# USB3_Hub.net
KiCad netlist of a schematic drawn in EAGLE
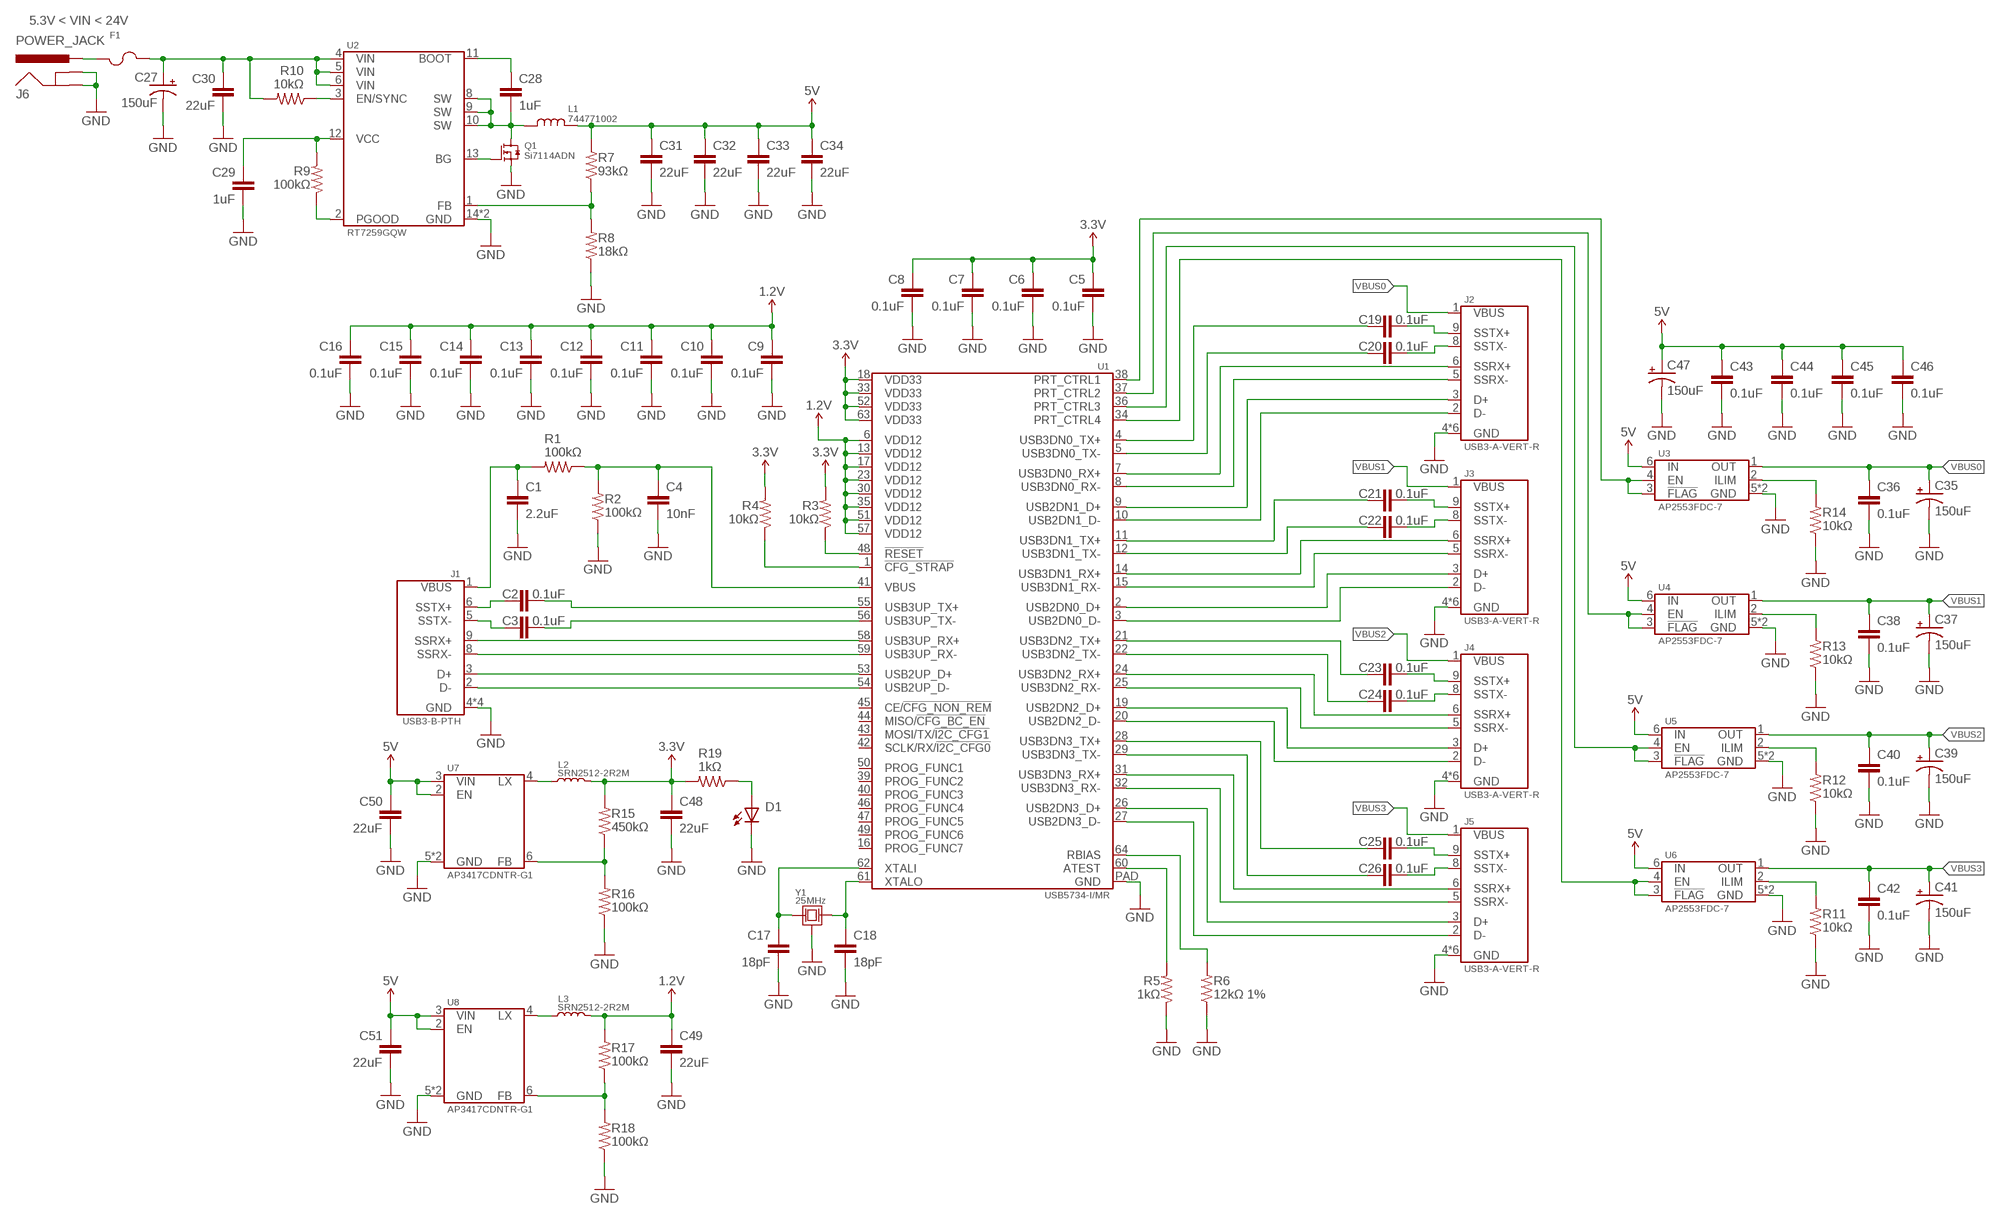
[diagram p0: schematic, sheet 1]

(export (version "E")
  (design (tool "Eeschema 10.0.6"))
  (components
    (comp (ref "C1")
      (value "2.2uF")
      (footprint "eagle-import:0603-CAP")
      (libsource (lib "eagle-import") (part "CAP-0603"))
    )
    (comp (ref "C2")
      (value "0.1uF")
      (footprint "eagle-import:0603-CAP")
      (libsource (lib "eagle-import") (part "CAP-0603"))
    )
    (comp (ref "C3")
      (value "0.1uF")
      (footprint "eagle-import:0603-CAP")
      (libsource (lib "eagle-import") (part "CAP-0603"))
    )
    (comp (ref "C4")
      (value "10nF")
      (footprint "eagle-import:0603-CAP")
      (libsource (lib "eagle-import") (part "CAP-0603"))
    )
    (comp (ref "C5")
      (value "0.1uF")
      (footprint "eagle-import:0603-CAP")
      (libsource (lib "eagle-import") (part "CAP-0603"))
    )
    (comp (ref "C6")
      (value "0.1uF")
      (footprint "eagle-import:0603-CAP")
      (libsource (lib "eagle-import") (part "CAP-0603"))
    )
    (comp (ref "C7")
      (value "0.1uF")
      (footprint "eagle-import:0603-CAP")
      (libsource (lib "eagle-import") (part "CAP-0603"))
    )
    (comp (ref "C8")
      (value "0.1uF")
      (footprint "eagle-import:0603-CAP")
      (libsource (lib "eagle-import") (part "CAP-0603"))
    )
    (comp (ref "C9")
      (value "0.1uF")
      (footprint "eagle-import:0603-CAP")
      (libsource (lib "eagle-import") (part "CAP-0603"))
    )
    (comp (ref "C10")
      (value "0.1uF")
      (footprint "eagle-import:0603-CAP")
      (libsource (lib "eagle-import") (part "CAP-0603"))
    )
    (comp (ref "C11")
      (value "0.1uF")
      (footprint "eagle-import:0603-CAP")
      (libsource (lib "eagle-import") (part "CAP-0603"))
    )
    (comp (ref "C12")
      (value "0.1uF")
      (footprint "eagle-import:0603-CAP")
      (libsource (lib "eagle-import") (part "CAP-0603"))
    )
    (comp (ref "C13")
      (value "0.1uF")
      (footprint "eagle-import:0603-CAP")
      (libsource (lib "eagle-import") (part "CAP-0603"))
    )
    (comp (ref "C14")
      (value "0.1uF")
      (footprint "eagle-import:0603-CAP")
      (libsource (lib "eagle-import") (part "CAP-0603"))
    )
    (comp (ref "C15")
      (value "0.1uF")
      (footprint "eagle-import:0603-CAP")
      (libsource (lib "eagle-import") (part "CAP-0603"))
    )
    (comp (ref "C16")
      (value "0.1uF")
      (footprint "eagle-import:0603-CAP")
      (libsource (lib "eagle-import") (part "CAP-0603"))
    )
    (comp (ref "C17")
      (value "18pF")
      (footprint "eagle-import:0603-CAP")
      (libsource (lib "eagle-import") (part "CAP-0603"))
    )
    (comp (ref "C18")
      (value "18pF")
      (footprint "eagle-import:0603-CAP")
      (libsource (lib "eagle-import") (part "CAP-0603"))
    )
    (comp (ref "C19")
      (value "0.1uF")
      (footprint "eagle-import:0603-CAP")
      (libsource (lib "eagle-import") (part "CAP-0603"))
    )
    (comp (ref "C20")
      (value "0.1uF")
      (footprint "eagle-import:0603-CAP")
      (libsource (lib "eagle-import") (part "CAP-0603"))
    )
    (comp (ref "C21")
      (value "0.1uF")
      (footprint "eagle-import:0603-CAP")
      (libsource (lib "eagle-import") (part "CAP-0603"))
    )
    (comp (ref "C22")
      (value "0.1uF")
      (footprint "eagle-import:0603-CAP")
      (libsource (lib "eagle-import") (part "CAP-0603"))
    )
    (comp (ref "C23")
      (value "0.1uF")
      (footprint "eagle-import:0603-CAP")
      (libsource (lib "eagle-import") (part "CAP-0603"))
    )
    (comp (ref "C24")
      (value "0.1uF")
      (footprint "eagle-import:0603-CAP")
      (libsource (lib "eagle-import") (part "CAP-0603"))
    )
    (comp (ref "C25")
      (value "0.1uF")
      (footprint "eagle-import:0603-CAP")
      (libsource (lib "eagle-import") (part "CAP-0603"))
    )
    (comp (ref "C26")
      (value "0.1uF")
      (footprint "eagle-import:0603-CAP")
      (libsource (lib "eagle-import") (part "CAP-0603"))
    )
    (comp (ref "C27")
      (value "150uF")
      (footprint "eagle-import:CAP_POL-6.6X6.6")
      (libsource (lib "eagle-import") (part "CAP_POL-6.6X6.6"))
    )
    (comp (ref "C28")
      (value "1uF")
      (footprint "eagle-import:0603-CAP")
      (libsource (lib "eagle-import") (part "CAP-0603"))
    )
    (comp (ref "C29")
      (value "1uF")
      (footprint "eagle-import:0603-CAP")
      (libsource (lib "eagle-import") (part "CAP-0603"))
    )
    (comp (ref "C30")
      (value "22uF")
      (footprint "eagle-import:0603-CAP")
      (libsource (lib "eagle-import") (part "CAP-0603"))
    )
    (comp (ref "C31")
      (value "22uF")
      (footprint "eagle-import:0603-CAP")
      (libsource (lib "eagle-import") (part "CAP-0603"))
    )
    (comp (ref "C32")
      (value "22uF")
      (footprint "eagle-import:0603-CAP")
      (libsource (lib "eagle-import") (part "CAP-0603"))
    )
    (comp (ref "C33")
      (value "22uF")
      (footprint "eagle-import:0603-CAP")
      (libsource (lib "eagle-import") (part "CAP-0603"))
    )
    (comp (ref "C34")
      (value "22uF")
      (footprint "eagle-import:0603-CAP")
      (libsource (lib "eagle-import") (part "CAP-0603"))
    )
    (comp (ref "C35")
      (value "150uF")
      (footprint "eagle-import:CAP_POL-6.6X6.6")
      (libsource (lib "eagle-import") (part "CAP_POL-6.6X6.6"))
    )
    (comp (ref "C36")
      (value "0.1uF")
      (footprint "eagle-import:0603-CAP")
      (libsource (lib "eagle-import") (part "CAP-0603"))
    )
    (comp (ref "C37")
      (value "150uF")
      (footprint "eagle-import:CAP_POL-6.6X6.6")
      (libsource (lib "eagle-import") (part "CAP_POL-6.6X6.6"))
    )
    (comp (ref "C38")
      (value "0.1uF")
      (footprint "eagle-import:0603-CAP")
      (libsource (lib "eagle-import") (part "CAP-0603"))
    )
    (comp (ref "C39")
      (value "150uF")
      (footprint "eagle-import:CAP_POL-6.6X6.6")
      (libsource (lib "eagle-import") (part "CAP_POL-6.6X6.6"))
    )
    (comp (ref "C40")
      (value "0.1uF")
      (footprint "eagle-import:0603-CAP")
      (libsource (lib "eagle-import") (part "CAP-0603"))
    )
    (comp (ref "C41")
      (value "150uF")
      (footprint "eagle-import:CAP_POL-6.6X6.6")
      (libsource (lib "eagle-import") (part "CAP_POL-6.6X6.6"))
    )
    (comp (ref "C42")
      (value "0.1uF")
      (footprint "eagle-import:0603-CAP")
      (libsource (lib "eagle-import") (part "CAP-0603"))
    )
    (comp (ref "C43")
      (value "0.1uF")
      (footprint "eagle-import:0603-CAP")
      (libsource (lib "eagle-import") (part "CAP-0603"))
    )
    (comp (ref "C44")
      (value "0.1uF")
      (footprint "eagle-import:0603-CAP")
      (libsource (lib "eagle-import") (part "CAP-0603"))
    )
    (comp (ref "C45")
      (value "0.1uF")
      (footprint "eagle-import:0603-CAP")
      (libsource (lib "eagle-import") (part "CAP-0603"))
    )
    (comp (ref "C46")
      (value "0.1uF")
      (footprint "eagle-import:0603-CAP")
      (libsource (lib "eagle-import") (part "CAP-0603"))
    )
    (comp (ref "C47")
      (value "150uF")
      (footprint "eagle-import:CAP_POL-6.6X6.6")
      (libsource (lib "eagle-import") (part "CAP_POL-6.6X6.6"))
    )
    (comp (ref "C48")
      (value "22uF")
      (footprint "eagle-import:0603-CAP")
      (libsource (lib "eagle-import") (part "CAP-0603"))
    )
    (comp (ref "C49")
      (value "22uF")
      (footprint "eagle-import:0603-CAP")
      (libsource (lib "eagle-import") (part "CAP-0603"))
    )
    (comp (ref "C50")
      (value "22uF")
      (footprint "eagle-import:0603-CAP")
      (libsource (lib "eagle-import") (part "CAP-0603"))
    )
    (comp (ref "C51")
      (value "22uF")
      (footprint "eagle-import:0603-CAP")
      (libsource (lib "eagle-import") (part "CAP-0603"))
    )
    (comp (ref "D1")
      (value "LED-0805")
      (footprint "eagle-import:0805-LED")
      (libsource (lib "eagle-import") (part "LED-0805"))
    )
    (comp (ref "F1")
      (value "PTC-1812")
      (footprint "eagle-import:1812-PTC")
      (libsource (lib "eagle-import") (part "PTC-1812"))
    )
    (comp (ref "J1")
      (value "USB3-B-PTH")
      (footprint "eagle-import:GSB4211311WEU")
      (libsource (lib "eagle-import") (part "USB3-B-PTH"))
    )
    (comp (ref "J2")
      (value "USB3-A-VERT-R")
      (footprint "eagle-import:GSB4116341HR")
      (libsource (lib "eagle-import") (part "USB3-A-VERT-R"))
    )
    (comp (ref "J3")
      (value "USB3-A-VERT-R")
      (footprint "eagle-import:GSB4116341HR")
      (libsource (lib "eagle-import") (part "USB3-A-VERT-R"))
    )
    (comp (ref "J4")
      (value "USB3-A-VERT-R")
      (footprint "eagle-import:GSB4116341HR")
      (libsource (lib "eagle-import") (part "USB3-A-VERT-R"))
    )
    (comp (ref "J5")
      (value "USB3-A-VERT-R")
      (footprint "eagle-import:GSB4116341HR")
      (libsource (lib "eagle-import") (part "USB3-A-VERT-R"))
    )
    (comp (ref "J6")
      (value "POWER_JACK")
      (footprint "eagle-import:BARREL-POWER_2.1MMX5.5MM")
      (libsource (lib "eagle-import") (part "POWER_JACK"))
    )
    (comp (ref "L1")
      (value "744771002")
      (footprint "eagle-import:744771002")
      (libsource (lib "eagle-import") (part "INDUCTOR-744771002"))
    )
    (comp (ref "L2")
      (value "SRN2512-2R2M")
      (footprint "eagle-import:SRN2512")
      (libsource (lib "eagle-import") (part "SRN2512-2R2M"))
    )
    (comp (ref "L3")
      (value "SRN2512-2R2M")
      (footprint "eagle-import:SRN2512")
      (libsource (lib "eagle-import") (part "SRN2512-2R2M"))
    )
    (comp (ref "Q1")
      (value "Si7114ADN")
      (footprint "eagle-import:POWERPAK")
      (libsource (lib "eagle-import") (part "N-MOSFET"))
    )
    (comp (ref "R1")
      (value "100kΩ")
      (footprint "eagle-import:0603-CAP")
      (libsource (lib "eagle-import") (part "RESISTOR-0603"))
    )
    (comp (ref "R2")
      (value "100kΩ")
      (footprint "eagle-import:0603-CAP")
      (libsource (lib "eagle-import") (part "RESISTOR-0603"))
    )
    (comp (ref "R3")
      (value "10kΩ")
      (footprint "eagle-import:0603-CAP")
      (libsource (lib "eagle-import") (part "RESISTOR-0603"))
    )
    (comp (ref "R4")
      (value "10kΩ")
      (footprint "eagle-import:0603-CAP")
      (libsource (lib "eagle-import") (part "RESISTOR-0603"))
    )
    (comp (ref "R5")
      (value "1kΩ")
      (footprint "eagle-import:0603-CAP")
      (libsource (lib "eagle-import") (part "RESISTOR-0603"))
    )
    (comp (ref "R6")
      (value "12kΩ 1%")
      (footprint "eagle-import:0603-CAP")
      (libsource (lib "eagle-import") (part "RESISTOR-0603"))
    )
    (comp (ref "R7")
      (value "93kΩ")
      (footprint "eagle-import:0603-CAP")
      (libsource (lib "eagle-import") (part "RESISTOR-0603"))
    )
    (comp (ref "R8")
      (value "18kΩ")
      (footprint "eagle-import:0603-CAP")
      (libsource (lib "eagle-import") (part "RESISTOR-0603"))
    )
    (comp (ref "R9")
      (value "100kΩ")
      (footprint "eagle-import:0603-CAP")
      (libsource (lib "eagle-import") (part "RESISTOR-0603"))
    )
    (comp (ref "R10")
      (value "10kΩ")
      (footprint "eagle-import:0603-CAP")
      (libsource (lib "eagle-import") (part "RESISTOR-0603"))
    )
    (comp (ref "R11")
      (value "10kΩ")
      (footprint "eagle-import:0603-CAP")
      (libsource (lib "eagle-import") (part "RESISTOR-0603"))
    )
    (comp (ref "R12")
      (value "10kΩ")
      (footprint "eagle-import:0603-CAP")
      (libsource (lib "eagle-import") (part "RESISTOR-0603"))
    )
    (comp (ref "R13")
      (value "10kΩ")
      (footprint "eagle-import:0603-CAP")
      (libsource (lib "eagle-import") (part "RESISTOR-0603"))
    )
    (comp (ref "R14")
      (value "10kΩ")
      (footprint "eagle-import:0603-CAP")
      (libsource (lib "eagle-import") (part "RESISTOR-0603"))
    )
    (comp (ref "R15")
      (value "450kΩ")
      (footprint "eagle-import:0603-CAP")
      (libsource (lib "eagle-import") (part "RESISTOR-0603"))
    )
    (comp (ref "R16")
      (value "100kΩ")
      (footprint "eagle-import:0603-CAP")
      (libsource (lib "eagle-import") (part "RESISTOR-0603"))
    )
    (comp (ref "R17")
      (value "100kΩ")
      (footprint "eagle-import:0603-CAP")
      (libsource (lib "eagle-import") (part "RESISTOR-0603"))
    )
    (comp (ref "R18")
      (value "100kΩ")
      (footprint "eagle-import:0603-CAP")
      (libsource (lib "eagle-import") (part "RESISTOR-0603"))
    )
    (comp (ref "R19")
      (value "1kΩ")
      (footprint "eagle-import:0603-CAP")
      (libsource (lib "eagle-import") (part "RESISTOR-0603"))
    )
    (comp (ref "U1")
      (value "USB5734-I/MR")
      (footprint "eagle-import:VQFN-64-9MM")
      (libsource (lib "eagle-import") (part "USB5734-I/MR"))
    )
    (comp (ref "U2")
      (value "RT7259GQW")
      (footprint "eagle-import:WDFN-14-4X3")
      (libsource (lib "eagle-import") (part "RT7259GQW"))
    )
    (comp (ref "U3")
      (value "AP2553FDC-7")
      (footprint "eagle-import:UDFN6-2020")
      (libsource (lib "eagle-import") (part "AP2553FDC-7"))
    )
    (comp (ref "U4")
      (value "AP2553FDC-7")
      (footprint "eagle-import:UDFN6-2020")
      (libsource (lib "eagle-import") (part "AP2553FDC-7"))
    )
    (comp (ref "U5")
      (value "AP2553FDC-7")
      (footprint "eagle-import:UDFN6-2020")
      (libsource (lib "eagle-import") (part "AP2553FDC-7"))
    )
    (comp (ref "U6")
      (value "AP2553FDC-7")
      (footprint "eagle-import:UDFN6-2020")
      (libsource (lib "eagle-import") (part "AP2553FDC-7"))
    )
    (comp (ref "U7")
      (value "AP3417CDNTR-G1")
      (footprint "eagle-import:UDFN6-2020")
      (libsource (lib "eagle-import") (part "AP3417CDNTR-G1"))
    )
    (comp (ref "U8")
      (value "AP3417CDNTR-G1")
      (footprint "eagle-import:UDFN6-2020")
      (libsource (lib "eagle-import") (part "AP3417CDNTR-G1"))
    )
    (comp (ref "Y1")
      (value "25MHz")
      (footprint "eagle-import:FA-238")
      (libsource (lib "eagle-import") (part "CRYSTAL-3.2X2.5"))
    )
  )
  (nets
    (net (code "1") (name "1.2V") (class "Default")
      (node (ref "C10") (pin "1") (pinfunction "1_1") (pintype "passive"))
      (node (ref "C11") (pin "1") (pinfunction "1_1") (pintype "passive"))
      (node (ref "C12") (pin "1") (pinfunction "1_1") (pintype "passive"))
      (node (ref "C13") (pin "1") (pinfunction "1_1") (pintype "passive"))
      (node (ref "C14") (pin "1") (pinfunction "1_1") (pintype "passive"))
      (node (ref "C15") (pin "1") (pinfunction "1_1") (pintype "passive"))
      (node (ref "C16") (pin "1") (pinfunction "1_1") (pintype "passive"))
      (node (ref "C49") (pin "1") (pinfunction "1_1") (pintype "passive"))
      (node (ref "C9") (pin "1") (pinfunction "1_1") (pintype "passive"))
      (node (ref "L3") (pin "2") (pinfunction "2_2") (pintype "bidirectional"))
      (node (ref "R17") (pin "2") (pinfunction "2_2") (pintype "passive"))
      (node (ref "U1") (pin "13") (pinfunction "VDD12_13") (pintype "bidirectional"))
      (node (ref "U1") (pin "17") (pinfunction "VDD12_17") (pintype "bidirectional"))
      (node (ref "U1") (pin "23") (pinfunction "VDD12_23") (pintype "bidirectional"))
      (node (ref "U1") (pin "30") (pinfunction "VDD12_30") (pintype "bidirectional"))
      (node (ref "U1") (pin "35") (pinfunction "VDD12_35") (pintype "bidirectional"))
      (node (ref "U1") (pin "51") (pinfunction "VDD12_51") (pintype "bidirectional"))
      (node (ref "U1") (pin "57") (pinfunction "VDD12_57") (pintype "bidirectional"))
      (node (ref "U1") (pin "6") (pinfunction "VDD12_6") (pintype "bidirectional"))
    )
    (net (code "2") (name "3.3V") (class "Default")
      (node (ref "C48") (pin "1") (pinfunction "1_1") (pintype "passive"))
      (node (ref "C5") (pin "1") (pinfunction "1_1") (pintype "passive"))
      (node (ref "C6") (pin "1") (pinfunction "1_1") (pintype "passive"))
      (node (ref "C7") (pin "1") (pinfunction "1_1") (pintype "passive"))
      (node (ref "C8") (pin "1") (pinfunction "1_1") (pintype "passive"))
      (node (ref "L2") (pin "2") (pinfunction "2_2") (pintype "bidirectional"))
      (node (ref "R15") (pin "2") (pinfunction "2_2") (pintype "passive"))
      (node (ref "R19") (pin "2") (pinfunction "2_2") (pintype "passive"))
      (node (ref "R3") (pin "2") (pinfunction "2_2") (pintype "passive"))
      (node (ref "R4") (pin "2") (pinfunction "2_2") (pintype "passive"))
      (node (ref "U1") (pin "18") (pinfunction "VDD33_18") (pintype "bidirectional"))
      (node (ref "U1") (pin "33") (pinfunction "VDD33_33") (pintype "bidirectional"))
      (node (ref "U1") (pin "52") (pinfunction "VDD33_52") (pintype "bidirectional"))
      (node (ref "U1") (pin "63") (pinfunction "VDD33_63") (pintype "bidirectional"))
    )
    (net (code "3") (name "5V") (class "Default")
      (node (ref "C31") (pin "1") (pinfunction "1_1") (pintype "passive"))
      (node (ref "C32") (pin "1") (pinfunction "1_1") (pintype "passive"))
      (node (ref "C33") (pin "1") (pinfunction "1_1") (pintype "passive"))
      (node (ref "C34") (pin "1") (pinfunction "1_1") (pintype "passive"))
      (node (ref "C43") (pin "1") (pinfunction "1_1") (pintype "passive"))
      (node (ref "C44") (pin "1") (pinfunction "1_1") (pintype "passive"))
      (node (ref "C45") (pin "1") (pinfunction "1_1") (pintype "passive"))
      (node (ref "C46") (pin "1") (pinfunction "1_1") (pintype "passive"))
      (node (ref "C47") (pin "+") (pinfunction "+_+") (pintype "passive"))
      (node (ref "C50") (pin "1") (pinfunction "1_1") (pintype "passive"))
      (node (ref "C51") (pin "1") (pinfunction "1_1") (pintype "passive"))
      (node (ref "L1") (pin "P$2") (pinfunction "P$2_P$2") (pintype "bidirectional"))
      (node (ref "R7") (pin "2") (pinfunction "2_2") (pintype "passive"))
      (node (ref "U3") (pin "6") (pinfunction "IN_6") (pintype "bidirectional"))
      (node (ref "U4") (pin "6") (pinfunction "IN_6") (pintype "bidirectional"))
      (node (ref "U5") (pin "6") (pinfunction "IN_6") (pintype "bidirectional"))
      (node (ref "U6") (pin "6") (pinfunction "IN_6") (pintype "bidirectional"))
      (node (ref "U7") (pin "2") (pinfunction "EN_2") (pintype "bidirectional"))
      (node (ref "U7") (pin "3") (pinfunction "VIN_3") (pintype "bidirectional"))
      (node (ref "U8") (pin "2") (pinfunction "EN_2") (pintype "bidirectional"))
      (node (ref "U8") (pin "3") (pinfunction "VIN_3") (pintype "bidirectional"))
    )
    (net (code "4") (name "GND") (class "Default")
      (node (ref "C1") (pin "2") (pinfunction "2_2") (pintype "passive"))
      (node (ref "C10") (pin "2") (pinfunction "2_2") (pintype "passive"))
      (node (ref "C11") (pin "2") (pinfunction "2_2") (pintype "passive"))
      (node (ref "C12") (pin "2") (pinfunction "2_2") (pintype "passive"))
      (node (ref "C13") (pin "2") (pinfunction "2_2") (pintype "passive"))
      (node (ref "C14") (pin "2") (pinfunction "2_2") (pintype "passive"))
      (node (ref "C15") (pin "2") (pinfunction "2_2") (pintype "passive"))
      (node (ref "C16") (pin "2") (pinfunction "2_2") (pintype "passive"))
      (node (ref "C17") (pin "2") (pinfunction "2_2") (pintype "passive"))
      (node (ref "C18") (pin "2") (pinfunction "2_2") (pintype "passive"))
      (node (ref "C27") (pin "-") (pinfunction "-_-") (pintype "passive"))
      (node (ref "C29") (pin "2") (pinfunction "2_2") (pintype "passive"))
      (node (ref "C30") (pin "2") (pinfunction "2_2") (pintype "passive"))
      (node (ref "C31") (pin "2") (pinfunction "2_2") (pintype "passive"))
      (node (ref "C32") (pin "2") (pinfunction "2_2") (pintype "passive"))
      (node (ref "C33") (pin "2") (pinfunction "2_2") (pintype "passive"))
      (node (ref "C34") (pin "2") (pinfunction "2_2") (pintype "passive"))
      (node (ref "C35") (pin "-") (pinfunction "-_-") (pintype "passive"))
      (node (ref "C36") (pin "2") (pinfunction "2_2") (pintype "passive"))
      (node (ref "C37") (pin "-") (pinfunction "-_-") (pintype "passive"))
      (node (ref "C38") (pin "2") (pinfunction "2_2") (pintype "passive"))
      (node (ref "C39") (pin "-") (pinfunction "-_-") (pintype "passive"))
      (node (ref "C4") (pin "2") (pinfunction "2_2") (pintype "passive"))
      (node (ref "C40") (pin "2") (pinfunction "2_2") (pintype "passive"))
      (node (ref "C41") (pin "-") (pinfunction "-_-") (pintype "passive"))
      (node (ref "C42") (pin "2") (pinfunction "2_2") (pintype "passive"))
      (node (ref "C43") (pin "2") (pinfunction "2_2") (pintype "passive"))
      (node (ref "C44") (pin "2") (pinfunction "2_2") (pintype "passive"))
      (node (ref "C45") (pin "2") (pinfunction "2_2") (pintype "passive"))
      (node (ref "C46") (pin "2") (pinfunction "2_2") (pintype "passive"))
      (node (ref "C47") (pin "-") (pinfunction "-_-") (pintype "passive"))
      (node (ref "C48") (pin "2") (pinfunction "2_2") (pintype "passive"))
      (node (ref "C49") (pin "2") (pinfunction "2_2") (pintype "passive"))
      (node (ref "C5") (pin "2") (pinfunction "2_2") (pintype "passive"))
      (node (ref "C50") (pin "2") (pinfunction "2_2") (pintype "passive"))
      (node (ref "C51") (pin "2") (pinfunction "2_2") (pintype "passive"))
      (node (ref "C6") (pin "2") (pinfunction "2_2") (pintype "passive"))
      (node (ref "C7") (pin "2") (pinfunction "2_2") (pintype "passive"))
      (node (ref "C8") (pin "2") (pinfunction "2_2") (pintype "passive"))
      (node (ref "C9") (pin "2") (pinfunction "2_2") (pintype "passive"))
      (node (ref "D1") (pin "C") (pinfunction "C_C") (pintype "passive"))
      (node (ref "J1") (pin "4") (pinfunction "GND_4") (pintype "bidirectional"))
      (node (ref "J1") (pin "7") (pinfunction "GND_7") (pintype "bidirectional"))
      (node (ref "J1") (pin "P$10") (pinfunction "GND_P$10") (pintype "bidirectional"))
      (node (ref "J1") (pin "P$11") (pinfunction "GND_P$11") (pintype "bidirectional"))
      (node (ref "J2") (pin "4") (pinfunction "GND_4") (pintype "bidirectional"))
      (node (ref "J2") (pin "7") (pinfunction "GND_7") (pintype "bidirectional"))
      (node (ref "J2") (pin "P$1") (pinfunction "GND_P$1") (pintype "bidirectional"))
      (node (ref "J2") (pin "P$2") (pinfunction "GND_P$2") (pintype "bidirectional"))
      (node (ref "J2") (pin "P$3") (pinfunction "GND_P$3") (pintype "bidirectional"))
      (node (ref "J2") (pin "P$4") (pinfunction "GND_P$4") (pintype "bidirectional"))
      (node (ref "J3") (pin "4") (pinfunction "GND_4") (pintype "bidirectional"))
      (node (ref "J3") (pin "7") (pinfunction "GND_7") (pintype "bidirectional"))
      (node (ref "J3") (pin "P$1") (pinfunction "GND_P$1") (pintype "bidirectional"))
      (node (ref "J3") (pin "P$2") (pinfunction "GND_P$2") (pintype "bidirectional"))
      (node (ref "J3") (pin "P$3") (pinfunction "GND_P$3") (pintype "bidirectional"))
      (node (ref "J3") (pin "P$4") (pinfunction "GND_P$4") (pintype "bidirectional"))
      (node (ref "J4") (pin "4") (pinfunction "GND_4") (pintype "bidirectional"))
      (node (ref "J4") (pin "7") (pinfunction "GND_7") (pintype "bidirectional"))
      (node (ref "J4") (pin "P$1") (pinfunction "GND_P$1") (pintype "bidirectional"))
      (node (ref "J4") (pin "P$2") (pinfunction "GND_P$2") (pintype "bidirectional"))
      (node (ref "J4") (pin "P$3") (pinfunction "GND_P$3") (pintype "bidirectional"))
      (node (ref "J4") (pin "P$4") (pinfunction "GND_P$4") (pintype "bidirectional"))
      (node (ref "J5") (pin "4") (pinfunction "GND_4") (pintype "bidirectional"))
      (node (ref "J5") (pin "7") (pinfunction "GND_7") (pintype "bidirectional"))
      (node (ref "J5") (pin "P$1") (pinfunction "GND_P$1") (pintype "bidirectional"))
      (node (ref "J5") (pin "P$2") (pinfunction "GND_P$2") (pintype "bidirectional"))
      (node (ref "J5") (pin "P$3") (pinfunction "GND_P$3") (pintype "bidirectional"))
      (node (ref "J5") (pin "P$4") (pinfunction "GND_P$4") (pintype "bidirectional"))
      (node (ref "J6") (pin "2") (pinfunction "GND_2") (pintype "bidirectional"))
      (node (ref "J6") (pin "3") (pinfunction "GNDBREAK_3") (pintype "bidirectional"))
      (node (ref "Q1") (pin "1") (pinfunction "SOURCE_1") (pintype "bidirectional"))
      (node (ref "Q1") (pin "2") (pinfunction "SOURCE_2") (pintype "bidirectional"))
      (node (ref "Q1") (pin "3") (pinfunction "SOURCE_3") (pintype "bidirectional"))
      (node (ref "R11") (pin "1") (pinfunction "1_1") (pintype "passive"))
      (node (ref "R12") (pin "1") (pinfunction "1_1") (pintype "passive"))
      (node (ref "R13") (pin "1") (pinfunction "1_1") (pintype "passive"))
      (node (ref "R14") (pin "1") (pinfunction "1_1") (pintype "passive"))
      (node (ref "R16") (pin "1") (pinfunction "1_1") (pintype "passive"))
      (node (ref "R18") (pin "1") (pinfunction "1_1") (pintype "passive"))
      (node (ref "R2") (pin "1") (pinfunction "1_1") (pintype "passive"))
      (node (ref "R5") (pin "1") (pinfunction "1_1") (pintype "passive"))
      (node (ref "R6") (pin "1") (pinfunction "1_1") (pintype "passive"))
      (node (ref "R8") (pin "1") (pinfunction "1_1") (pintype "passive"))
      (node (ref "U1") (pin "PAD") (pinfunction "GND_PAD") (pintype "bidirectional"))
      (node (ref "U2") (pin "14") (pinfunction "GND_14") (pintype "bidirectional"))
      (node (ref "U2") (pin "PAD") (pinfunction "GND_PAD") (pintype "bidirectional"))
      (node (ref "U3") (pin "5") (pinfunction "GND_5") (pintype "bidirectional"))
      (node (ref "U3") (pin "PAD") (pinfunction "GND_PAD") (pintype "bidirectional"))
      (node (ref "U4") (pin "5") (pinfunction "GND_5") (pintype "bidirectional"))
      (node (ref "U4") (pin "PAD") (pinfunction "GND_PAD") (pintype "bidirectional"))
      (node (ref "U5") (pin "5") (pinfunction "GND_5") (pintype "bidirectional"))
      (node (ref "U5") (pin "PAD") (pinfunction "GND_PAD") (pintype "bidirectional"))
      (node (ref "U6") (pin "5") (pinfunction "GND_5") (pintype "bidirectional"))
      (node (ref "U6") (pin "PAD") (pinfunction "GND_PAD") (pintype "bidirectional"))
      (node (ref "U7") (pin "5") (pinfunction "GND_5") (pintype "bidirectional"))
      (node (ref "U7") (pin "PAD") (pinfunction "GND_PAD") (pintype "bidirectional"))
      (node (ref "U8") (pin "5") (pinfunction "GND_5") (pintype "bidirectional"))
      (node (ref "U8") (pin "PAD") (pinfunction "GND_PAD") (pintype "bidirectional"))
      (node (ref "Y1") (pin "2") (pinfunction "GND_2") (pintype "bidirectional"))
      (node (ref "Y1") (pin "4") (pinfunction "GND_4") (pintype "bidirectional"))
    )
    (net (code "5") (name "Net-(C27-Pad+)") (class "Default")
      (node (ref "C27") (pin "+") (pinfunction "+_+") (pintype "passive"))
      (node (ref "C30") (pin "1") (pinfunction "1_1") (pintype "passive"))
      (node (ref "F1") (pin "2") (pinfunction "2_2") (pintype "bidirectional"))
      (node (ref "R10") (pin "2") (pinfunction "2_2") (pintype "passive"))
      (node (ref "U2") (pin "4") (pinfunction "VIN_4") (pintype "bidirectional"))
      (node (ref "U2") (pin "5") (pinfunction "VIN_5") (pintype "bidirectional"))
      (node (ref "U2") (pin "6") (pinfunction "VIN_6") (pintype "bidirectional"))
    )
    (net (code "6") (name "Net-(C28-Pad2)") (class "Default")
      (node (ref "C28") (pin "2") (pinfunction "2_2") (pintype "passive"))
      (node (ref "L1") (pin "P$1") (pinfunction "P$1_P$1") (pintype "bidirectional"))
      (node (ref "Q1") (pin "10") (pinfunction "DRAIN_10") (pintype "bidirectional"))
      (node (ref "Q1") (pin "11") (pinfunction "DRAIN_11") (pintype "bidirectional"))
      (node (ref "Q1") (pin "5") (pinfunction "DRAIN_5") (pintype "bidirectional"))
      (node (ref "Q1") (pin "6") (pinfunction "DRAIN_6") (pintype "bidirectional"))
      (node (ref "Q1") (pin "7") (pinfunction "DRAIN_7") (pintype "bidirectional"))
      (node (ref "Q1") (pin "8") (pinfunction "DRAIN_8") (pintype "bidirectional"))
      (node (ref "Q1") (pin "9") (pinfunction "DRAIN_9") (pintype "bidirectional"))
      (node (ref "U2") (pin "10") (pinfunction "SW_10") (pintype "bidirectional"))
      (node (ref "U2") (pin "8") (pinfunction "SW_8") (pintype "bidirectional"))
      (node (ref "U2") (pin "9") (pinfunction "SW_9") (pintype "bidirectional"))
    )
    (net (code "7") (name "Net-(D1-PadA)") (class "Default")
      (node (ref "D1") (pin "A") (pinfunction "A_A") (pintype "passive"))
      (node (ref "R19") (pin "1") (pinfunction "1_1") (pintype "passive"))
    )
    (net (code "8") (name "Net-(J1-D+)") (class "Default")
      (node (ref "J1") (pin "3") (pinfunction "D+_3") (pintype "bidirectional"))
      (node (ref "U1") (pin "53") (pinfunction "USB2UP_D+_53") (pintype "bidirectional"))
    )
    (net (code "9") (name "Net-(J1-D-)") (class "Default")
      (node (ref "J1") (pin "2") (pinfunction "D-_2") (pintype "bidirectional"))
      (node (ref "U1") (pin "54") (pinfunction "USB2UP_D-_54") (pintype "bidirectional"))
    )
    (net (code "10") (name "Net-(J1-SSRX+)") (class "Default")
      (node (ref "J1") (pin "9") (pinfunction "SSRX+_9") (pintype "bidirectional"))
      (node (ref "U1") (pin "58") (pinfunction "USB3UP_RX+_58") (pintype "bidirectional"))
    )
    (net (code "11") (name "Net-(J1-SSRX-)") (class "Default")
      (node (ref "J1") (pin "8") (pinfunction "SSRX-_8") (pintype "bidirectional"))
      (node (ref "U1") (pin "59") (pinfunction "USB3UP_RX-_59") (pintype "bidirectional"))
    )
    (net (code "12") (name "Net-(J1-SSTX+)") (class "Default")
      (node (ref "C2") (pin "1") (pinfunction "1_1") (pintype "passive"))
      (node (ref "J1") (pin "6") (pinfunction "SSTX+_6") (pintype "bidirectional"))
    )
    (net (code "13") (name "Net-(J1-SSTX-)") (class "Default")
      (node (ref "C3") (pin "1") (pinfunction "1_1") (pintype "passive"))
      (node (ref "J1") (pin "5") (pinfunction "SSTX-_5") (pintype "bidirectional"))
    )
    (net (code "14") (name "Net-(J1-VBUS)") (class "Default")
      (node (ref "C1") (pin "1") (pinfunction "1_1") (pintype "passive"))
      (node (ref "J1") (pin "1") (pinfunction "VBUS_1") (pintype "bidirectional"))
      (node (ref "R1") (pin "2") (pinfunction "2_2") (pintype "passive"))
    )
    (net (code "15") (name "Net-(J2-D+)") (class "Default")
      (node (ref "J2") (pin "3") (pinfunction "D+_3") (pintype "bidirectional"))
      (node (ref "U1") (pin "9") (pinfunction "USB2DN1_D+_9") (pintype "bidirectional"))
    )
    (net (code "16") (name "Net-(J2-D-)") (class "Default")
      (node (ref "J2") (pin "2") (pinfunction "D-_2") (pintype "bidirectional"))
      (node (ref "U1") (pin "10") (pinfunction "USB2DN1_D-_10") (pintype "bidirectional"))
    )
    (net (code "17") (name "Net-(J2-SSRX+)") (class "Default")
      (node (ref "J2") (pin "6") (pinfunction "SSRX+_6") (pintype "bidirectional"))
      (node (ref "U1") (pin "7") (pinfunction "USB3DN0_RX+_7") (pintype "bidirectional"))
    )
    (net (code "18") (name "Net-(J2-SSRX-)") (class "Default")
      (node (ref "J2") (pin "5") (pinfunction "SSRX-_5") (pintype "bidirectional"))
      (node (ref "U1") (pin "8") (pinfunction "USB3DN0_RX-_8") (pintype "bidirectional"))
    )
    (net (code "19") (name "Net-(J2-SSTX+)") (class "Default")
      (node (ref "C19") (pin "2") (pinfunction "2_2") (pintype "passive"))
      (node (ref "J2") (pin "9") (pinfunction "SSTX+_9") (pintype "bidirectional"))
    )
    (net (code "20") (name "Net-(J2-SSTX-)") (class "Default")
      (node (ref "C20") (pin "2") (pinfunction "2_2") (pintype "passive"))
      (node (ref "J2") (pin "8") (pinfunction "SSTX-_8") (pintype "bidirectional"))
    )
    (net (code "21") (name "Net-(J3-D+)") (class "Default")
      (node (ref "J3") (pin "3") (pinfunction "D+_3") (pintype "bidirectional"))
      (node (ref "U1") (pin "2") (pinfunction "USB2DN0_D+_2") (pintype "bidirectional"))
    )
    (net (code "22") (name "Net-(J3-D-)") (class "Default")
      (node (ref "J3") (pin "2") (pinfunction "D-_2") (pintype "bidirectional"))
      (node (ref "U1") (pin "3") (pinfunction "USB2DN0_D-_3") (pintype "bidirectional"))
    )
    (net (code "23") (name "Net-(J3-SSRX+)") (class "Default")
      (node (ref "J3") (pin "6") (pinfunction "SSRX+_6") (pintype "bidirectional"))
      (node (ref "U1") (pin "14") (pinfunction "USB3DN1_RX+_14") (pintype "bidirectional"))
    )
    (net (code "24") (name "Net-(J3-SSRX-)") (class "Default")
      (node (ref "J3") (pin "5") (pinfunction "SSRX-_5") (pintype "bidirectional"))
      (node (ref "U1") (pin "15") (pinfunction "USB3DN1_RX-_15") (pintype "bidirectional"))
    )
    (net (code "25") (name "Net-(J3-SSTX+)") (class "Default")
      (node (ref "C21") (pin "2") (pinfunction "2_2") (pintype "passive"))
      (node (ref "J3") (pin "9") (pinfunction "SSTX+_9") (pintype "bidirectional"))
    )
    (net (code "26") (name "Net-(J3-SSTX-)") (class "Default")
      (node (ref "C22") (pin "2") (pinfunction "2_2") (pintype "passive"))
      (node (ref "J3") (pin "8") (pinfunction "SSTX-_8") (pintype "bidirectional"))
    )
    (net (code "27") (name "Net-(J4-D+)") (class "Default")
      (node (ref "J4") (pin "3") (pinfunction "D+_3") (pintype "bidirectional"))
      (node (ref "U1") (pin "19") (pinfunction "USB2DN2_D+_19") (pintype "bidirectional"))
    )
    (net (code "28") (name "Net-(J4-D-)") (class "Default")
      (node (ref "J4") (pin "2") (pinfunction "D-_2") (pintype "bidirectional"))
      (node (ref "U1") (pin "20") (pinfunction "USB2DN2_D-_20") (pintype "bidirectional"))
    )
    (net (code "29") (name "Net-(J4-SSRX+)") (class "Default")
      (node (ref "J4") (pin "6") (pinfunction "SSRX+_6") (pintype "bidirectional"))
      (node (ref "U1") (pin "24") (pinfunction "USB3DN2_RX+_24") (pintype "bidirectional"))
    )
    (net (code "30") (name "Net-(J4-SSRX-)") (class "Default")
      (node (ref "J4") (pin "5") (pinfunction "SSRX-_5") (pintype "bidirectional"))
      (node (ref "U1") (pin "25") (pinfunction "USB3DN2_RX-_25") (pintype "bidirectional"))
    )
    (net (code "31") (name "Net-(J4-SSTX+)") (class "Default")
      (node (ref "C23") (pin "2") (pinfunction "2_2") (pintype "passive"))
      (node (ref "J4") (pin "9") (pinfunction "SSTX+_9") (pintype "bidirectional"))
    )
    (net (code "32") (name "Net-(J4-SSTX-)") (class "Default")
      (node (ref "C24") (pin "2") (pinfunction "2_2") (pintype "passive"))
      (node (ref "J4") (pin "8") (pinfunction "SSTX-_8") (pintype "bidirectional"))
    )
    (net (code "33") (name "Net-(J5-D+)") (class "Default")
      (node (ref "J5") (pin "3") (pinfunction "D+_3") (pintype "bidirectional"))
      (node (ref "U1") (pin "26") (pinfunction "USB2DN3_D+_26") (pintype "bidirectional"))
    )
    (net (code "34") (name "Net-(J5-D-)") (class "Default")
      (node (ref "J5") (pin "2") (pinfunction "D-_2") (pintype "bidirectional"))
      (node (ref "U1") (pin "27") (pinfunction "USB2DN3_D-_27") (pintype "bidirectional"))
    )
    (net (code "35") (name "Net-(J5-SSRX+)") (class "Default")
      (node (ref "J5") (pin "6") (pinfunction "SSRX+_6") (pintype "bidirectional"))
      (node (ref "U1") (pin "31") (pinfunction "USB3DN3_RX+_31") (pintype "bidirectional"))
    )
    (net (code "36") (name "Net-(J5-SSRX-)") (class "Default")
      (node (ref "J5") (pin "5") (pinfunction "SSRX-_5") (pintype "bidirectional"))
      (node (ref "U1") (pin "32") (pinfunction "USB3DN3_RX-_32") (pintype "bidirectional"))
    )
    (net (code "37") (name "Net-(J5-SSTX+)") (class "Default")
      (node (ref "C25") (pin "2") (pinfunction "2_2") (pintype "passive"))
      (node (ref "J5") (pin "9") (pinfunction "SSTX+_9") (pintype "bidirectional"))
    )
    (net (code "38") (name "Net-(J5-SSTX-)") (class "Default")
      (node (ref "C26") (pin "2") (pinfunction "2_2") (pintype "passive"))
      (node (ref "J5") (pin "8") (pinfunction "SSTX-_8") (pintype "bidirectional"))
    )
    (net (code "39") (name "Net-(J6-PWR)") (class "Default")
      (node (ref "F1") (pin "1") (pinfunction "1_1") (pintype "bidirectional"))
      (node (ref "J6") (pin "1") (pinfunction "PWR_1") (pintype "bidirectional"))
    )
    (net (code "40") (name "Net-(Q1-GATE)") (class "Default")
      (node (ref "Q1") (pin "4") (pinfunction "GATE_4") (pintype "bidirectional"))
      (node (ref "U2") (pin "13") (pinfunction "BG_13") (pintype "bidirectional"))
    )
    (net (code "41") (name "Net-(U1-ATEST)") (class "Default")
      (node (ref "R5") (pin "2") (pinfunction "2_2") (pintype "passive"))
      (node (ref "U1") (pin "60") (pinfunction "ATEST_60") (pintype "bidirectional"))
    )
    (net (code "42") (name "Net-(U1-PRT_CTRL1)") (class "Default")
      (node (ref "U1") (pin "38") (pinfunction "PRT_CTRL1_38") (pintype "bidirectional"))
      (node (ref "U3") (pin "3") (pinfunction "~{FLAG}_3") (pintype "bidirectional"))
      (node (ref "U3") (pin "4") (pinfunction "EN_4") (pintype "bidirectional"))
    )
    (net (code "43") (name "Net-(U1-PRT_CTRL2)") (class "Default")
      (node (ref "U1") (pin "37") (pinfunction "PRT_CTRL2_37") (pintype "bidirectional"))
      (node (ref "U4") (pin "3") (pinfunction "~{FLAG}_3") (pintype "bidirectional"))
      (node (ref "U4") (pin "4") (pinfunction "EN_4") (pintype "bidirectional"))
    )
    (net (code "44") (name "Net-(U1-PRT_CTRL3)") (class "Default")
      (node (ref "U1") (pin "36") (pinfunction "PRT_CTRL3_36") (pintype "bidirectional"))
      (node (ref "U5") (pin "3") (pinfunction "~{FLAG}_3") (pintype "bidirectional"))
      (node (ref "U5") (pin "4") (pinfunction "EN_4") (pintype "bidirectional"))
    )
    (net (code "45") (name "Net-(U1-PRT_CTRL4)") (class "Default")
      (node (ref "U1") (pin "34") (pinfunction "PRT_CTRL4_34") (pintype "bidirectional"))
      (node (ref "U6") (pin "3") (pinfunction "~{FLAG}_3") (pintype "bidirectional"))
      (node (ref "U6") (pin "4") (pinfunction "EN_4") (pintype "bidirectional"))
    )
    (net (code "46") (name "Net-(U1-RBIAS)") (class "Default")
      (node (ref "R6") (pin "2") (pinfunction "2_2") (pintype "passive"))
      (node (ref "U1") (pin "64") (pinfunction "RBIAS_64") (pintype "bidirectional"))
    )
    (net (code "47") (name "Net-(U1-USB3DN0_TX+)") (class "Default")
      (node (ref "C19") (pin "1") (pinfunction "1_1") (pintype "passive"))
      (node (ref "U1") (pin "4") (pinfunction "USB3DN0_TX+_4") (pintype "bidirectional"))
    )
    (net (code "48") (name "Net-(U1-USB3DN0_TX-)") (class "Default")
      (node (ref "C20") (pin "1") (pinfunction "1_1") (pintype "passive"))
      (node (ref "U1") (pin "5") (pinfunction "USB3DN0_TX-_5") (pintype "bidirectional"))
    )
    (net (code "49") (name "Net-(U1-USB3DN1_TX+)") (class "Default")
      (node (ref "C21") (pin "1") (pinfunction "1_1") (pintype "passive"))
      (node (ref "U1") (pin "11") (pinfunction "USB3DN1_TX+_11") (pintype "bidirectional"))
    )
    (net (code "50") (name "Net-(U1-USB3DN1_TX-)") (class "Default")
      (node (ref "C22") (pin "1") (pinfunction "1_1") (pintype "passive"))
      (node (ref "U1") (pin "12") (pinfunction "USB3DN1_TX-_12") (pintype "bidirectional"))
    )
    (net (code "51") (name "Net-(U1-USB3DN2_TX+)") (class "Default")
      (node (ref "C23") (pin "1") (pinfunction "1_1") (pintype "passive"))
      (node (ref "U1") (pin "21") (pinfunction "USB3DN2_TX+_21") (pintype "bidirectional"))
    )
    (net (code "52") (name "Net-(U1-USB3DN2_TX-)") (class "Default")
      (node (ref "C24") (pin "1") (pinfunction "1_1") (pintype "passive"))
      (node (ref "U1") (pin "22") (pinfunction "USB3DN2_TX-_22") (pintype "bidirectional"))
    )
    (net (code "53") (name "Net-(U1-USB3DN3_TX+)") (class "Default")
      (node (ref "C25") (pin "1") (pinfunction "1_1") (pintype "passive"))
      (node (ref "U1") (pin "28") (pinfunction "USB3DN3_TX+_28") (pintype "bidirectional"))
    )
    (net (code "54") (name "Net-(U1-USB3DN3_TX-)") (class "Default")
      (node (ref "C26") (pin "1") (pinfunction "1_1") (pintype "passive"))
      (node (ref "U1") (pin "29") (pinfunction "USB3DN3_TX-_29") (pintype "bidirectional"))
    )
    (net (code "55") (name "Net-(U1-USB3UP_TX+)") (class "Default")
      (node (ref "C2") (pin "2") (pinfunction "2_2") (pintype "passive"))
      (node (ref "U1") (pin "55") (pinfunction "USB3UP_TX+_55") (pintype "bidirectional"))
    )
    (net (code "56") (name "Net-(U1-USB3UP_TX-)") (class "Default")
      (node (ref "C3") (pin "2") (pinfunction "2_2") (pintype "passive"))
      (node (ref "U1") (pin "56") (pinfunction "USB3UP_TX-_56") (pintype "bidirectional"))
    )
    (net (code "57") (name "Net-(U1-VBUS)") (class "Default")
      (node (ref "C4") (pin "1") (pinfunction "1_1") (pintype "passive"))
      (node (ref "R1") (pin "1") (pinfunction "1_1") (pintype "passive"))
      (node (ref "R2") (pin "2") (pinfunction "2_2") (pintype "passive"))
      (node (ref "U1") (pin "41") (pinfunction "VBUS_41") (pintype "bidirectional"))
    )
    (net (code "58") (name "Net-(U1-XTALI)") (class "Default")
      (node (ref "C17") (pin "1") (pinfunction "1_1") (pintype "passive"))
      (node (ref "U1") (pin "62") (pinfunction "XTALI_62") (pintype "bidirectional"))
      (node (ref "Y1") (pin "1") (pinfunction "1_1") (pintype "bidirectional"))
    )
    (net (code "59") (name "Net-(U1-XTALO)") (class "Default")
      (node (ref "C18") (pin "1") (pinfunction "1_1") (pintype "passive"))
      (node (ref "U1") (pin "61") (pinfunction "XTALO_61") (pintype "bidirectional"))
      (node (ref "Y1") (pin "3") (pinfunction "2_3") (pintype "bidirectional"))
    )
    (net (code "60") (name "Net-(U1-~{CFG_STRAP})") (class "Default")
      (node (ref "R4") (pin "1") (pinfunction "1_1") (pintype "passive"))
      (node (ref "U1") (pin "1") (pinfunction "~{CFG_STRAP}_1") (pintype "bidirectional"))
    )
    (net (code "61") (name "Net-(U1-~{RESET})") (class "Default")
      (node (ref "R3") (pin "1") (pinfunction "1_1") (pintype "passive"))
      (node (ref "U1") (pin "48") (pinfunction "~{RESET}_48") (pintype "bidirectional"))
    )
    (net (code "62") (name "Net-(U2-BOOT)") (class "Default")
      (node (ref "C28") (pin "1") (pinfunction "1_1") (pintype "passive"))
      (node (ref "U2") (pin "11") (pinfunction "BOOT_11") (pintype "bidirectional"))
    )
    (net (code "63") (name "Net-(U2-EN{slash}SYNC)") (class "Default")
      (node (ref "R10") (pin "1") (pinfunction "1_1") (pintype "passive"))
      (node (ref "U2") (pin "3") (pinfunction "EN/SYNC_3") (pintype "bidirectional"))
    )
    (net (code "64") (name "Net-(U2-FB)") (class "Default")
      (node (ref "R7") (pin "1") (pinfunction "1_1") (pintype "passive"))
      (node (ref "R8") (pin "2") (pinfunction "2_2") (pintype "passive"))
      (node (ref "U2") (pin "1") (pinfunction "FB_1") (pintype "bidirectional"))
    )
    (net (code "65") (name "Net-(U2-PGOOD)") (class "Default")
      (node (ref "R9") (pin "1") (pinfunction "1_1") (pintype "passive"))
      (node (ref "U2") (pin "2") (pinfunction "PGOOD_2") (pintype "bidirectional"))
    )
    (net (code "66") (name "Net-(U2-VCC)") (class "Default")
      (node (ref "C29") (pin "1") (pinfunction "1_1") (pintype "passive"))
      (node (ref "R9") (pin "2") (pinfunction "2_2") (pintype "passive"))
      (node (ref "U2") (pin "12") (pinfunction "VCC_12") (pintype "bidirectional"))
    )
    (net (code "67") (name "Net-(U3-ILIM)") (class "Default")
      (node (ref "R14") (pin "2") (pinfunction "2_2") (pintype "passive"))
      (node (ref "U3") (pin "2") (pinfunction "ILIM_2") (pintype "bidirectional"))
    )
    (net (code "68") (name "Net-(U4-ILIM)") (class "Default")
      (node (ref "R13") (pin "2") (pinfunction "2_2") (pintype "passive"))
      (node (ref "U4") (pin "2") (pinfunction "ILIM_2") (pintype "bidirectional"))
    )
    (net (code "69") (name "Net-(U5-ILIM)") (class "Default")
      (node (ref "R12") (pin "2") (pinfunction "2_2") (pintype "passive"))
      (node (ref "U5") (pin "2") (pinfunction "ILIM_2") (pintype "bidirectional"))
    )
    (net (code "70") (name "Net-(U6-ILIM)") (class "Default")
      (node (ref "R11") (pin "2") (pinfunction "2_2") (pintype "passive"))
      (node (ref "U6") (pin "2") (pinfunction "ILIM_2") (pintype "bidirectional"))
    )
    (net (code "71") (name "Net-(U7-FB)") (class "Default")
      (node (ref "R15") (pin "1") (pinfunction "1_1") (pintype "passive"))
      (node (ref "R16") (pin "2") (pinfunction "2_2") (pintype "passive"))
      (node (ref "U7") (pin "6") (pinfunction "FB_6") (pintype "bidirectional"))
    )
    (net (code "72") (name "Net-(U7-LX)") (class "Default")
      (node (ref "L2") (pin "1") (pinfunction "1_1") (pintype "bidirectional"))
      (node (ref "U7") (pin "4") (pinfunction "LX_4") (pintype "bidirectional"))
    )
    (net (code "73") (name "Net-(U8-FB)") (class "Default")
      (node (ref "R17") (pin "1") (pinfunction "1_1") (pintype "passive"))
      (node (ref "R18") (pin "2") (pinfunction "2_2") (pintype "passive"))
      (node (ref "U8") (pin "6") (pinfunction "FB_6") (pintype "bidirectional"))
    )
    (net (code "74") (name "Net-(U8-LX)") (class "Default")
      (node (ref "L3") (pin "1") (pinfunction "1_1") (pintype "bidirectional"))
      (node (ref "U8") (pin "4") (pinfunction "LX_4") (pintype "bidirectional"))
    )
    (net (code "75") (name "VBUS0") (class "Default")
      (node (ref "C35") (pin "+") (pinfunction "+_+") (pintype "passive"))
      (node (ref "C36") (pin "1") (pinfunction "1_1") (pintype "passive"))
      (node (ref "J2") (pin "1") (pinfunction "VBUS_1") (pintype "bidirectional"))
      (node (ref "U3") (pin "1") (pinfunction "OUT_1") (pintype "bidirectional"))
    )
    (net (code "76") (name "VBUS1") (class "Default")
      (node (ref "C37") (pin "+") (pinfunction "+_+") (pintype "passive"))
      (node (ref "C38") (pin "1") (pinfunction "1_1") (pintype "passive"))
      (node (ref "J3") (pin "1") (pinfunction "VBUS_1") (pintype "bidirectional"))
      (node (ref "U4") (pin "1") (pinfunction "OUT_1") (pintype "bidirectional"))
    )
    (net (code "77") (name "VBUS2") (class "Default")
      (node (ref "C39") (pin "+") (pinfunction "+_+") (pintype "passive"))
      (node (ref "C40") (pin "1") (pinfunction "1_1") (pintype "passive"))
      (node (ref "J4") (pin "1") (pinfunction "VBUS_1") (pintype "bidirectional"))
      (node (ref "U5") (pin "1") (pinfunction "OUT_1") (pintype "bidirectional"))
    )
    (net (code "78") (name "VBUS3") (class "Default")
      (node (ref "C41") (pin "+") (pinfunction "+_+") (pintype "passive"))
      (node (ref "C42") (pin "1") (pinfunction "1_1") (pintype "passive"))
      (node (ref "J5") (pin "1") (pinfunction "VBUS_1") (pintype "bidirectional"))
      (node (ref "U6") (pin "1") (pinfunction "OUT_1") (pintype "bidirectional"))
    )
    (net (code "79") (name "unconnected-(U1-CE{slash}~{CFG_NON_REM}-Pad45)") (class "Default")
      (node (ref "U1") (pin "45") (pinfunction "CE/~{CFG_NON_REM}_45") (pintype "bidirectional"))
    )
    (net (code "80") (name "unconnected-(U1-MISO{slash}~{CFG_BC_EN}-Pad44)") (class "Default")
      (node (ref "U1") (pin "44") (pinfunction "MISO/~{CFG_BC_EN}_44") (pintype "bidirectional"))
    )
    (net (code "81") (name "unconnected-(U1-MOSI{slash}TX{slash}~{I2C_CFG1}-Pad43)") (class "Default")
      (node (ref "U1") (pin "43") (pinfunction "MOSI/TX/~{I2C_CFG1}_43") (pintype "bidirectional"))
    )
    (net (code "82") (name "unconnected-(U1-PROG_FUNC1-Pad50)") (class "Default")
      (node (ref "U1") (pin "50") (pinfunction "PROG_FUNC1_50") (pintype "bidirectional"))
    )
    (net (code "83") (name "unconnected-(U1-PROG_FUNC2-Pad39)") (class "Default")
      (node (ref "U1") (pin "39") (pinfunction "PROG_FUNC2_39") (pintype "bidirectional"))
    )
    (net (code "84") (name "unconnected-(U1-PROG_FUNC3-Pad40)") (class "Default")
      (node (ref "U1") (pin "40") (pinfunction "PROG_FUNC3_40") (pintype "bidirectional"))
    )
    (net (code "85") (name "unconnected-(U1-PROG_FUNC4-Pad46)") (class "Default")
      (node (ref "U1") (pin "46") (pinfunction "PROG_FUNC4_46") (pintype "bidirectional"))
    )
    (net (code "86") (name "unconnected-(U1-PROG_FUNC5-Pad47)") (class "Default")
      (node (ref "U1") (pin "47") (pinfunction "PROG_FUNC5_47") (pintype "bidirectional"))
    )
    (net (code "87") (name "unconnected-(U1-PROG_FUNC6-Pad49)") (class "Default")
      (node (ref "U1") (pin "49") (pinfunction "PROG_FUNC6_49") (pintype "bidirectional"))
    )
    (net (code "88") (name "unconnected-(U1-PROG_FUNC7-Pad16)") (class "Default")
      (node (ref "U1") (pin "16") (pinfunction "PROG_FUNC7_16") (pintype "bidirectional"))
    )
    (net (code "89") (name "unconnected-(U1-SCLK{slash}RX{slash}~{I2C_CFG0}-Pad42)") (class "Default")
      (node (ref "U1") (pin "42") (pinfunction "SCLK/RX/~{I2C_CFG0}_42") (pintype "bidirectional"))
    )
  )
)
